# ad.net
KiCad netlist of a schematic drawn in Altium Designer
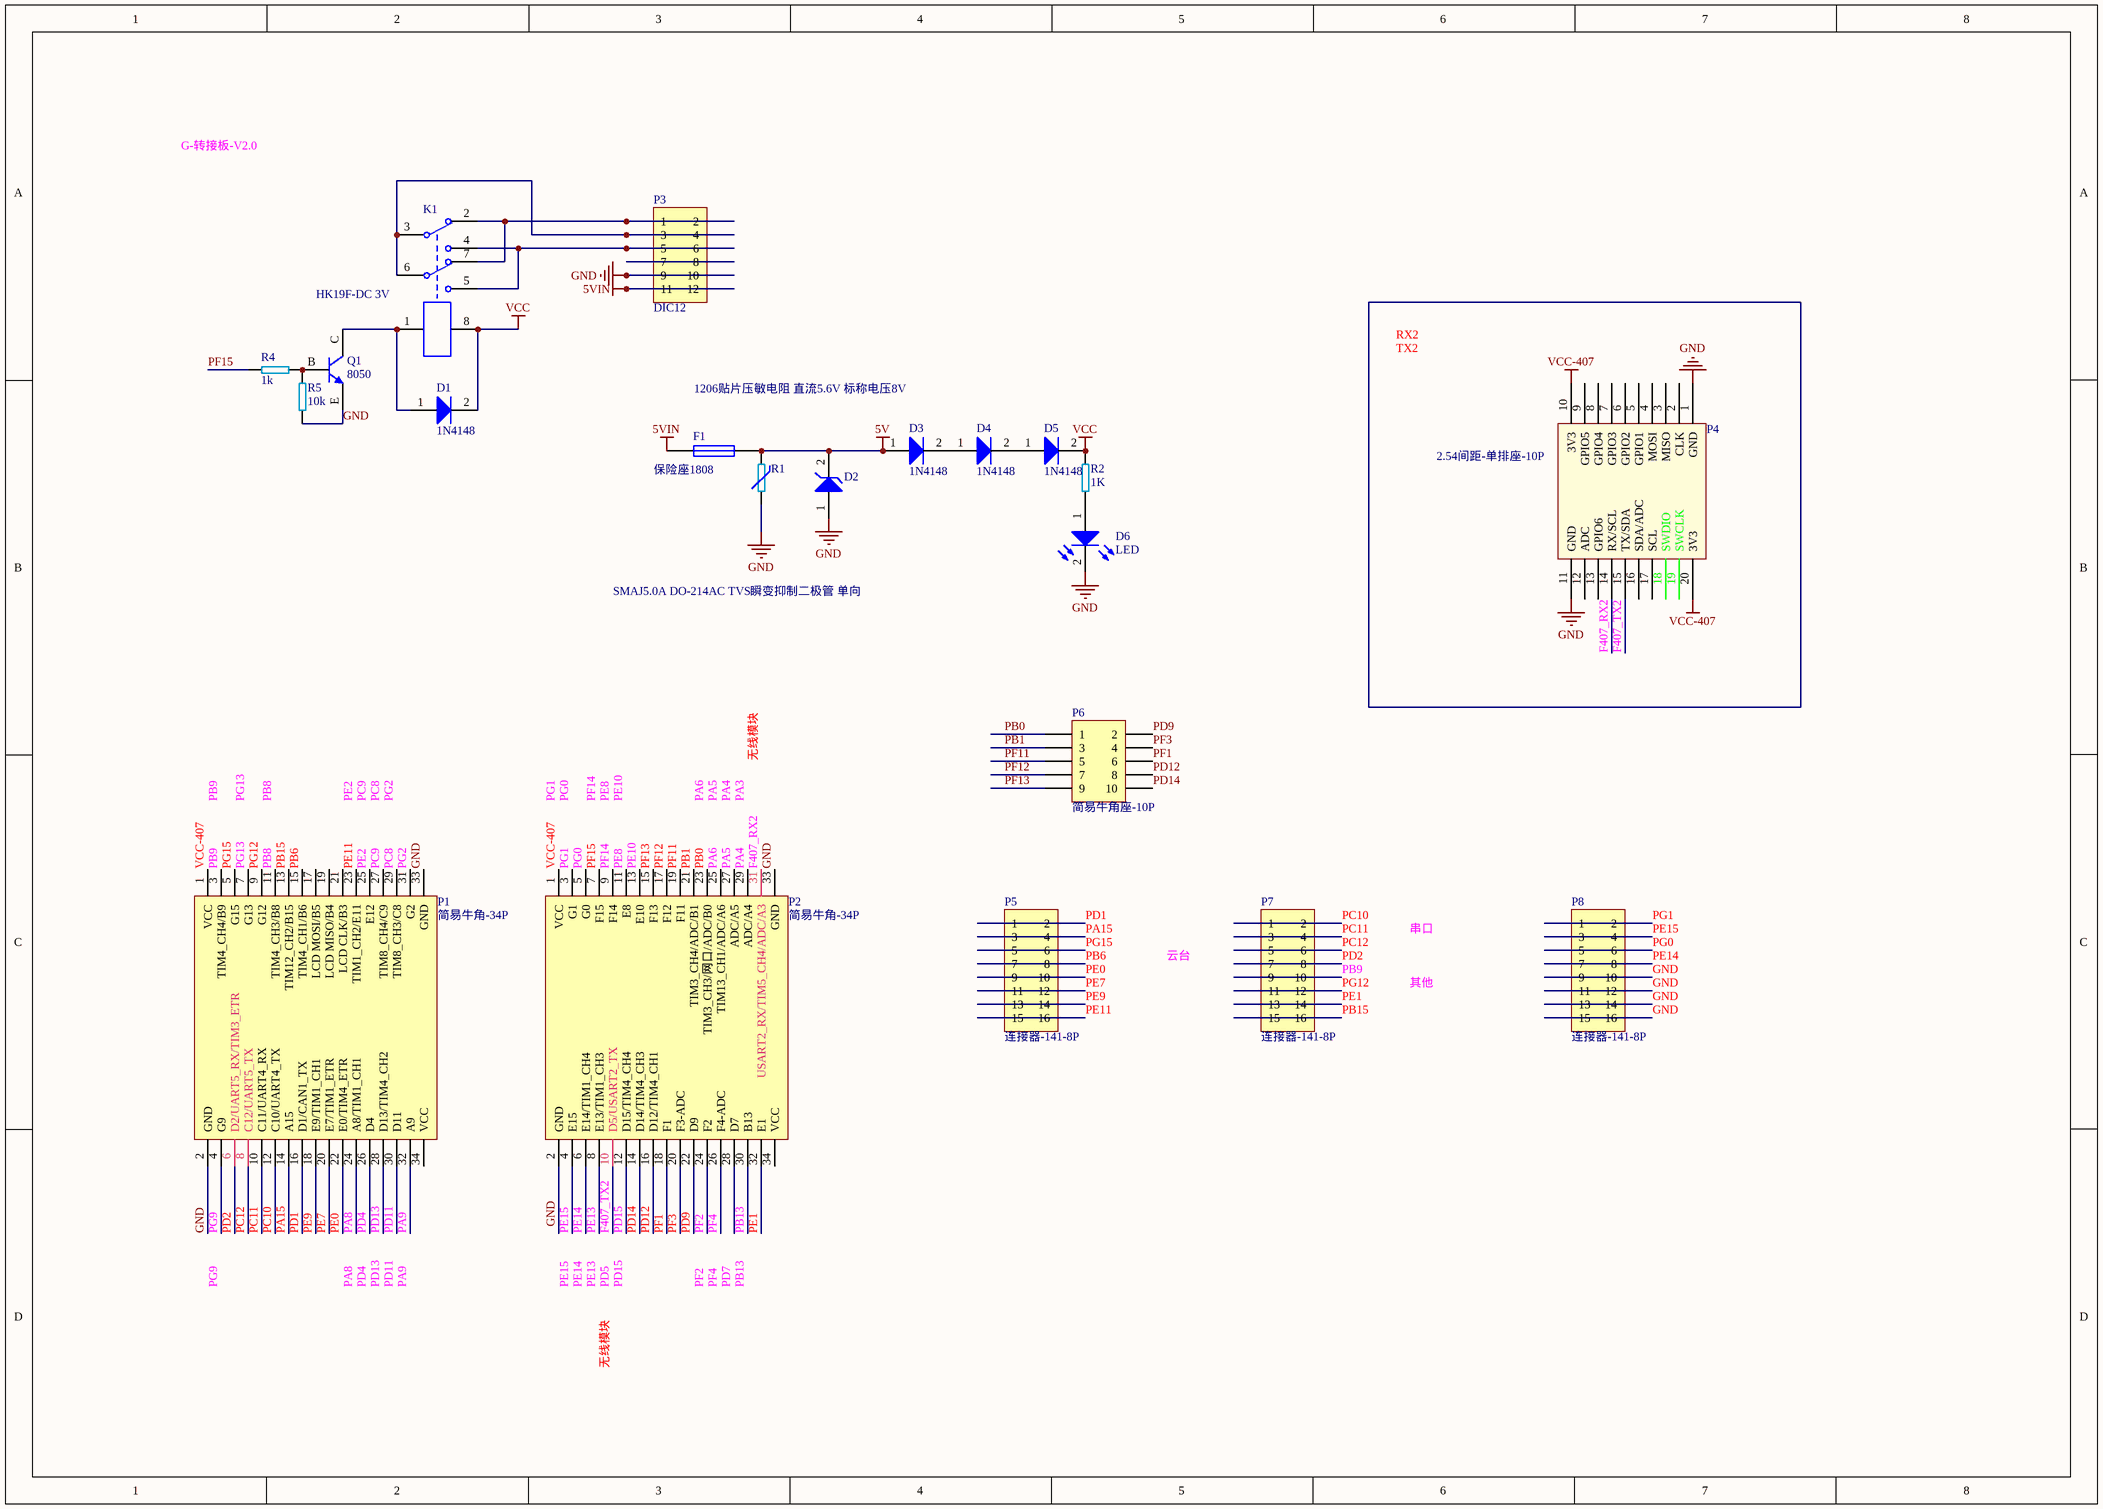
[diagram p0: ad.SchDoc]

(export (version "E")
  (design (tool "Eeschema 10.0.6"))
  (components
    (comp (ref "D1")
      (value "1N4148")
      (footprint "SOD123")
      (description "High Conductance Fast Diode")
      (fields (field (name "PUBLISHER") "Altium Limited"))
      (libsource (lib "base") (part "DD"))
    )
    (comp (ref "D2")
      (value "SMAJ5.0A DO-214AC TVS瞬变抑制二极管 单向")
      (footprint "SMA")
      (description "稳压管")
      (fields (field (name "PUBLISHER") "Altium Limited"))
      (libsource (lib "base") (part "TVS-SMA"))
    )
    (comp (ref "D3")
      (value "1N4148")
      (footprint "SOD123")
      (description "二极管")
      (fields (field (name "PUBLISHER") "Altium Limited"))
      (libsource (lib "base") (part "DD"))
    )
    (comp (ref "D4")
      (value "1N4148")
      (footprint "SOD123")
      (description "二极管")
      (fields (field (name "PUBLISHER") "Altium Limited"))
      (libsource (lib "base") (part "DD"))
    )
    (comp (ref "D5")
      (value "1N4148")
      (footprint "SOD123")
      (description "二极管")
      (fields (field (name "PUBLISHER") "Altium Limited"))
      (libsource (lib "base") (part "DD"))
    )
    (comp (ref "D6")
      (value "LED")
      (footprint "LED0603")
      (description "LED0603")
      (fields (field (name "PUBLISHER") "Altium Limited"))
      (libsource (lib "base") (part "LED0603"))
    )
    (comp (ref "F1")
      (value "保险座1808")
      (footprint "F1808-ZUO")
      (description "保险座")
      (fields (field (name "PUBLISHER") "Altium Limited"))
      (libsource (lib "base") (part "Fuse0805"))
    )
    (comp (ref "K1")
      (value "HK19F-DC 3V")
      (footprint "HK19F")
      (description "Dual-Pole Dual-Throw Relay")
      (fields (field (name "PUBLISHER") "Altium Limited"))
      (libsource (lib "base") (part "Relay-DPDT"))
    )
    (comp (ref "P1")
      (value "简易牛角-34P")
      (footprint "IDC2.54-LI-2x17P")
      (description "双排插座2.54间距-34P-带边框")
      (libsource (lib "base") (part "STM32F407-L"))
    )
    (comp (ref "P2")
      (value "简易牛角-34P")
      (footprint "IDC2.54-LI-2x17P")
      (description "双排插座2.54间距-34P-带边框")
      (libsource (lib "base") (part "STM32F407-R"))
    )
    (comp (ref "P3")
      (value "DIC12")
      (footprint "141V-6P")
      (description "连接器")
      (fields (field (name "PUBLISHER") "Altium Limited"))
      (libsource (lib "base") (part "DIC12"))
    )
    (comp (ref "P4")
      (value "2.54间距-单排座-10P")
      (footprint "SIP20-2-MODE")
      (description "单排针-10P")
      (libsource (lib "Schlib1") (part "PM-20-D"))
    )
    (comp (ref "P5")
      (value "连接器-141-8P")
      (footprint "141V-8P")
      (description "连接器")
      (fields (field (name "PUBLISHER") "Altium Limited"))
      (libsource (lib "base") (part "DIC16"))
    )
    (comp (ref "P6")
      (value "简易牛角座-10P")
      (footprint "IDC2.54-LI-10P")
      (description "连接器")
      (fields (field (name "PUBLISHER") "Altium Limited"))
      (libsource (lib "base") (part "DIC10"))
    )
    (comp (ref "P7")
      (value "连接器-141-8P")
      (footprint "141V-8P")
      (description "连接器")
      (fields (field (name "PUBLISHER") "Altium Limited"))
      (libsource (lib "base") (part "DIC16"))
    )
    (comp (ref "P8")
      (value "连接器-141-8P")
      (footprint "141V-8P")
      (description "连接器")
      (fields (field (name "PUBLISHER") "Altium Limited"))
      (libsource (lib "base") (part "DIC16"))
    )
    (comp (ref "Q1")
      (value "8050")
      (footprint "SOT-23")
      (description "NPN Bipolar Transistor")
      (fields (field (name "PUBLISHER") "Altium Limited"))
      (libsource (lib "base") (part "8050"))
    )
    (comp (ref "R1")
      (value "1206贴片压敏电阻 直流5.6V 标称电压8V")
      (footprint "R1206")
      (description "压敏电阻")
      (libsource (lib "base") (part "RV"))
    )
    (comp (ref "R2")
      (value "1K")
      (footprint "R0603")
      (description "贴片电阻")
      (libsource (lib "base") (part "R-0603"))
    )
    (comp (ref "R4") (value "1k") (footprint "R0603") (libsource (lib "base") (part "R-0603")))
    (comp (ref "R5")
      (value "10k")
      (footprint "R0603")
      (description "贴片电阻")
      (libsource (lib "base") (part "R-0603"))
    )
  )
  (nets
    (net (code "1") (name "/F407_RX2") (class "Default")
      (node (ref "P2") (pin "31") (pinfunction "USART2_RX/TIM5_CH4/ADC/A3_31") (pintype "passive"))
      (node (ref "P4") (pin "14") (pinfunction "RX/SCL_14") (pintype "passive"))
    )
    (net (code "2") (name "/F407_TX2") (class "Default")
      (node (ref "P2") (pin "10") (pinfunction "D5/USART2_TX_10") (pintype "passive"))
      (node (ref "P4") (pin "15") (pinfunction "TX/SDA_15") (pintype "passive"))
    )
    (net (code "5") (name "/PA4") (class "Default")
      (node (ref "P2") (pin "29") (pinfunction "ADC/A4_29") (pintype "passive"))
    )
    (net (code "6") (name "/PA5") (class "Default")
      (node (ref "P2") (pin "27") (pinfunction "ADC/A5_27") (pintype "passive"))
    )
    (net (code "7") (name "/PA6") (class "Default")
      (node (ref "P2") (pin "25") (pinfunction "TIM13_CH1/ADC/A6_25") (pintype "passive"))
    )
    (net (code "8") (name "/PA8") (class "Default")
      (node (ref "P1") (pin "24") (pinfunction "A8/TIM1_CH1_24") (pintype "passive"))
    )
    (net (code "9") (name "/PA9") (class "Default")
      (node (ref "P1") (pin "32") (pinfunction "A9_32") (pintype "passive"))
    )
    (net (code "10") (name "/PA15") (class "Default")
      (node (ref "P1") (pin "14") (pinfunction "A15_14") (pintype "passive"))
      (node (ref "P5") (pin "3") (pinfunction "3_3") (pintype "passive"))
      (node (ref "P5") (pin "4") (pinfunction "4_4") (pintype "passive"))
    )
    (net (code "11") (name "/PB0") (class "Default")
      (node (ref "P2") (pin "23") (pinfunction "TIM3_CH3/网口/ADC/B0_23") (pintype "passive"))
      (node (ref "P6") (pin "1") (pinfunction "1_1") (pintype "passive"))
    )
    (net (code "12") (name "/PB1") (class "Default")
      (node (ref "P2") (pin "21") (pinfunction "TIM3_CH4/ADC/B1_21") (pintype "passive"))
      (node (ref "P6") (pin "3") (pinfunction "3_3") (pintype "passive"))
    )
    (net (code "13") (name "/PB6") (class "Default")
      (node (ref "P1") (pin "15") (pinfunction "TIM4_CH1/B6_15") (pintype "passive"))
      (node (ref "P5") (pin "7") (pinfunction "7_7") (pintype "passive"))
      (node (ref "P5") (pin "8") (pinfunction "8_8") (pintype "passive"))
    )
    (net (code "14") (name "/PB8") (class "Default")
      (node (ref "P1") (pin "11") (pinfunction "TIM4_CH3/B8_11") (pintype "passive"))
    )
    (net (code "15") (name "/PB9") (class "Default")
      (node (ref "P1") (pin "3") (pinfunction "TIM4_CH4/B9_3") (pintype "passive"))
      (node (ref "P7") (pin "10") (pinfunction "10_10") (pintype "passive"))
      (node (ref "P7") (pin "9") (pinfunction "9_9") (pintype "passive"))
    )
    (net (code "16") (name "/PB13") (class "Default")
      (node (ref "P2") (pin "30") (pinfunction "B13_30") (pintype "passive"))
    )
    (net (code "17") (name "/PB15") (class "Default")
      (node (ref "P1") (pin "13") (pinfunction "TIM12_CH2/B15_13") (pintype "passive"))
      (node (ref "P7") (pin "15") (pinfunction "15_15") (pintype "passive"))
      (node (ref "P7") (pin "16") (pinfunction "16_16") (pintype "passive"))
    )
    (net (code "18") (name "/PC8") (class "Default")
      (node (ref "P1") (pin "29") (pinfunction "TIM8_CH3/C8_29") (pintype "passive"))
    )
    (net (code "19") (name "/PC9") (class "Default")
      (node (ref "P1") (pin "27") (pinfunction "TIM8_CH4/C9_27") (pintype "passive"))
    )
    (net (code "20") (name "/PC10") (class "Default")
      (node (ref "P1") (pin "12") (pinfunction "C10/UART4_TX_12") (pintype "passive"))
      (node (ref "P7") (pin "1") (pinfunction "1_1") (pintype "passive"))
      (node (ref "P7") (pin "2") (pinfunction "2_2") (pintype "passive"))
    )
    (net (code "21") (name "/PC11") (class "Default")
      (node (ref "P1") (pin "10") (pinfunction "C11/UART4_RX_10") (pintype "passive"))
      (node (ref "P7") (pin "3") (pinfunction "3_3") (pintype "passive"))
      (node (ref "P7") (pin "4") (pinfunction "4_4") (pintype "passive"))
    )
    (net (code "22") (name "/PC12") (class "Default")
      (node (ref "P1") (pin "8") (pinfunction "C12/UART5_TX_8") (pintype "passive"))
      (node (ref "P7") (pin "5") (pinfunction "5_5") (pintype "passive"))
      (node (ref "P7") (pin "6") (pinfunction "6_6") (pintype "passive"))
    )
    (net (code "23") (name "/PD1") (class "Default")
      (node (ref "P1") (pin "16") (pinfunction "D1/CAN1_TX_16") (pintype "passive"))
      (node (ref "P5") (pin "1") (pinfunction "1_1") (pintype "passive"))
      (node (ref "P5") (pin "2") (pinfunction "2_2") (pintype "passive"))
    )
    (net (code "24") (name "/PD2") (class "Default")
      (node (ref "P1") (pin "6") (pinfunction "D2/UART5_RX/TIM3_ETR_6") (pintype "passive"))
      (node (ref "P7") (pin "7") (pinfunction "7_7") (pintype "passive"))
      (node (ref "P7") (pin "8") (pinfunction "8_8") (pintype "passive"))
    )
    (net (code "25") (name "/PD4") (class "Default")
      (node (ref "P1") (pin "26") (pinfunction "D4_26") (pintype "passive"))
    )
    (net (code "28") (name "/PD9") (class "Default")
      (node (ref "P2") (pin "22") (pinfunction "D9_22") (pintype "passive"))
      (node (ref "P6") (pin "2") (pinfunction "2_2") (pintype "passive"))
    )
    (net (code "29") (name "/PD11") (class "Default")
      (node (ref "P1") (pin "30") (pinfunction "D11_30") (pintype "passive"))
    )
    (net (code "30") (name "/PD12") (class "Default")
      (node (ref "P2") (pin "16") (pinfunction "D12/TIM4_CH1_16") (pintype "passive"))
      (node (ref "P6") (pin "8") (pinfunction "8_8") (pintype "passive"))
    )
    (net (code "31") (name "/PD13") (class "Default")
      (node (ref "P1") (pin "28") (pinfunction "D13/TIM4_CH2_28") (pintype "passive"))
    )
    (net (code "32") (name "/PD14") (class "Default")
      (node (ref "P2") (pin "14") (pinfunction "D14/TIM4_CH3_14") (pintype "passive"))
      (node (ref "P6") (pin "10") (pinfunction "10_10") (pintype "passive"))
    )
    (net (code "33") (name "/PD15") (class "Default")
      (node (ref "P2") (pin "12") (pinfunction "D15/TIM4_CH4_12") (pintype "passive"))
    )
    (net (code "34") (name "/PE0") (class "Default")
      (node (ref "P1") (pin "22") (pinfunction "E0/TIM4_ETR_22") (pintype "passive"))
      (node (ref "P5") (pin "10") (pinfunction "10_10") (pintype "passive"))
      (node (ref "P5") (pin "9") (pinfunction "9_9") (pintype "passive"))
    )
    (net (code "35") (name "/PE1") (class "Default")
      (node (ref "P2") (pin "32") (pinfunction "E1_32") (pintype "passive"))
      (node (ref "P7") (pin "13") (pinfunction "13_13") (pintype "passive"))
      (node (ref "P7") (pin "14") (pinfunction "14_14") (pintype "passive"))
    )
    (net (code "36") (name "/PE2") (class "Default")
      (node (ref "P1") (pin "25") (pinfunction "E12_25") (pintype "passive"))
    )
    (net (code "37") (name "/PE7") (class "Default")
      (node (ref "P1") (pin "20") (pinfunction "E7/TIM1_ETR_20") (pintype "passive"))
      (node (ref "P5") (pin "11") (pinfunction "11_11") (pintype "passive"))
      (node (ref "P5") (pin "12") (pinfunction "12_12") (pintype "passive"))
    )
    (net (code "38") (name "/PE8") (class "Default")
      (node (ref "P2") (pin "11") (pinfunction "E8_11") (pintype "passive"))
    )
    (net (code "39") (name "/PE9") (class "Default")
      (node (ref "P1") (pin "18") (pinfunction "E9/TIM1_CH1_18") (pintype "passive"))
      (node (ref "P5") (pin "13") (pinfunction "13_13") (pintype "passive"))
      (node (ref "P5") (pin "14") (pinfunction "14_14") (pintype "passive"))
    )
    (net (code "40") (name "/PE10") (class "Default")
      (node (ref "P2") (pin "13") (pinfunction "E10_13") (pintype "passive"))
    )
    (net (code "41") (name "/PE11") (class "Default")
      (node (ref "P1") (pin "23") (pinfunction "TIM1_CH2/E11_23") (pintype "passive"))
      (node (ref "P5") (pin "15") (pinfunction "15_15") (pintype "passive"))
      (node (ref "P5") (pin "16") (pinfunction "16_16") (pintype "passive"))
    )
    (net (code "42") (name "/PE13") (class "Default")
      (node (ref "P2") (pin "8") (pinfunction "E13/TIM1_CH3_8") (pintype "passive"))
    )
    (net (code "43") (name "/PE14") (class "Default")
      (node (ref "P2") (pin "6") (pinfunction "E14/TIM1_CH4_6") (pintype "passive"))
      (node (ref "P8") (pin "7") (pinfunction "7_7") (pintype "passive"))
      (node (ref "P8") (pin "8") (pinfunction "8_8") (pintype "passive"))
    )
    (net (code "44") (name "/PE15") (class "Default")
      (node (ref "P2") (pin "4") (pinfunction "E15_4") (pintype "passive"))
      (node (ref "P8") (pin "3") (pinfunction "3_3") (pintype "passive"))
      (node (ref "P8") (pin "4") (pinfunction "4_4") (pintype "passive"))
    )
    (net (code "45") (name "/PF1") (class "Default")
      (node (ref "P2") (pin "18") (pinfunction "F1_18") (pintype "passive"))
      (node (ref "P6") (pin "6") (pinfunction "6_6") (pintype "passive"))
    )
    (net (code "46") (name "/PF2") (class "Default")
      (node (ref "P2") (pin "24") (pinfunction "F2_24") (pintype "passive"))
    )
    (net (code "47") (name "/PF3") (class "Default")
      (node (ref "P2") (pin "20") (pinfunction "F3-ADC_20") (pintype "passive"))
      (node (ref "P6") (pin "4") (pinfunction "4_4") (pintype "passive"))
    )
    (net (code "48") (name "/PF4") (class "Default")
      (node (ref "P2") (pin "26") (pinfunction "F4-ADC_26") (pintype "passive"))
    )
    (net (code "49") (name "/PF11") (class "Default")
      (node (ref "P2") (pin "19") (pinfunction "F11_19") (pintype "passive"))
      (node (ref "P6") (pin "5") (pinfunction "5_5") (pintype "passive"))
    )
    (net (code "50") (name "/PF12") (class "Default")
      (node (ref "P2") (pin "17") (pinfunction "F12_17") (pintype "passive"))
      (node (ref "P6") (pin "7") (pinfunction "7_7") (pintype "passive"))
    )
    (net (code "51") (name "/PF13") (class "Default")
      (node (ref "P2") (pin "15") (pinfunction "F13_15") (pintype "passive"))
      (node (ref "P6") (pin "9") (pinfunction "9_9") (pintype "passive"))
    )
    (net (code "52") (name "/PF14") (class "Default")
      (node (ref "P2") (pin "9") (pinfunction "F14_9") (pintype "passive"))
    )
    (net (code "53") (name "/PF15") (class "Default")
      (node (ref "P2") (pin "7") (pinfunction "F15_7") (pintype "passive"))
      (node (ref "R4") (pin "1") (pinfunction "1_1") (pintype "passive"))
    )
    (net (code "54") (name "/PG0") (class "Default")
      (node (ref "P2") (pin "5") (pinfunction "G0_5") (pintype "passive"))
      (node (ref "P8") (pin "5") (pinfunction "5_5") (pintype "passive"))
      (node (ref "P8") (pin "6") (pinfunction "6_6") (pintype "passive"))
    )
    (net (code "55") (name "/PG1") (class "Default")
      (node (ref "P2") (pin "3") (pinfunction "G1_3") (pintype "passive"))
      (node (ref "P8") (pin "1") (pinfunction "1_1") (pintype "passive"))
      (node (ref "P8") (pin "2") (pinfunction "2_2") (pintype "passive"))
    )
    (net (code "56") (name "/PG2") (class "Default")
      (node (ref "P1") (pin "31") (pinfunction "G2_31") (pintype "passive"))
    )
    (net (code "57") (name "/PG9") (class "Default")
      (node (ref "P1") (pin "4") (pinfunction "G9_4") (pintype "passive"))
    )
    (net (code "58") (name "/PG12") (class "Default")
      (node (ref "P1") (pin "9") (pinfunction "G12_9") (pintype "passive"))
      (node (ref "P7") (pin "11") (pinfunction "11_11") (pintype "passive"))
      (node (ref "P7") (pin "12") (pinfunction "12_12") (pintype "passive"))
    )
    (net (code "59") (name "/PG13") (class "Default")
      (node (ref "P1") (pin "7") (pinfunction "G13_7") (pintype "passive"))
    )
    (net (code "60") (name "/PG15") (class "Default")
      (node (ref "P1") (pin "5") (pinfunction "G15_5") (pintype "passive"))
      (node (ref "P5") (pin "5") (pinfunction "5_5") (pintype "passive"))
      (node (ref "P5") (pin "6") (pinfunction "6_6") (pintype "passive"))
    )
    (net (code "67") (name "5V") (class "Default")
      (node (ref "D2") (pin "2") (pinfunction "2_2") (pintype "passive"))
      (node (ref "D3") (pin "1") (pinfunction "A_1") (pintype "passive"))
      (node (ref "F1") (pin "2") (pinfunction "2_2") (pintype "passive"))
      (node (ref "R1") (pin "2") (pinfunction "2_2") (pintype "passive"))
    )
    (net (code "68") (name "5VIN") (class "Default")
      (node (ref "F1") (pin "1") (pinfunction "1_1") (pintype "passive"))
      (node (ref "P3") (pin "11") (pinfunction "11_11") (pintype "passive"))
      (node (ref "P3") (pin "12") (pinfunction "12_12") (pintype "passive"))
    )
    (net (code "69") (name "GND") (class "Default")
      (node (ref "D2") (pin "1") (pinfunction "1_1") (pintype "passive"))
      (node (ref "D6") (pin "2") (pinfunction "K_2") (pintype "passive"))
      (node (ref "P1") (pin "2") (pinfunction "GND_2") (pintype "passive"))
      (node (ref "P1") (pin "33") (pinfunction "GND_33") (pintype "passive"))
      (node (ref "P2") (pin "2") (pinfunction "GND_2") (pintype "passive"))
      (node (ref "P2") (pin "33") (pinfunction "GND_33") (pintype "passive"))
      (node (ref "P3") (pin "10") (pinfunction "10_10") (pintype "passive"))
      (node (ref "P3") (pin "9") (pinfunction "9_9") (pintype "passive"))
      (node (ref "P4") (pin "1") (pinfunction "GND_1") (pintype "passive"))
      (node (ref "P4") (pin "11") (pinfunction "GND_11") (pintype "passive"))
      (node (ref "P8") (pin "10") (pinfunction "10_10") (pintype "passive"))
      (node (ref "P8") (pin "11") (pinfunction "11_11") (pintype "passive"))
      (node (ref "P8") (pin "12") (pinfunction "12_12") (pintype "passive"))
      (node (ref "P8") (pin "13") (pinfunction "13_13") (pintype "passive"))
      (node (ref "P8") (pin "14") (pinfunction "14_14") (pintype "passive"))
      (node (ref "P8") (pin "15") (pinfunction "15_15") (pintype "passive"))
      (node (ref "P8") (pin "16") (pinfunction "16_16") (pintype "passive"))
      (node (ref "P8") (pin "9") (pinfunction "9_9") (pintype "passive"))
      (node (ref "Q1") (pin "E") (pinfunction "E_E") (pintype "passive"))
      (node (ref "R1") (pin "1") (pinfunction "1_1") (pintype "passive"))
      (node (ref "R5") (pin "1") (pinfunction "1_1") (pintype "passive"))
    )
    (net (code "70") (name "Net-(D1-A)") (class "Default")
      (node (ref "D1") (pin "1") (pinfunction "A_1") (pintype "passive"))
      (node (ref "K1") (pin "1") (pinfunction "1_1") (pintype "passive"))
      (node (ref "Q1") (pin "C") (pinfunction "C_C") (pintype "passive"))
    )
    (net (code "71") (name "Net-(D3-K)") (class "Default")
      (node (ref "D3") (pin "2") (pinfunction "K_2") (pintype "passive"))
      (node (ref "D4") (pin "1") (pinfunction "A_1") (pintype "passive"))
    )
    (net (code "72") (name "Net-(D4-K)") (class "Default")
      (node (ref "D4") (pin "2") (pinfunction "K_2") (pintype "passive"))
      (node (ref "D5") (pin "1") (pinfunction "A_1") (pintype "passive"))
    )
    (net (code "73") (name "Net-(D6-A)") (class "Default")
      (node (ref "D6") (pin "1") (pinfunction "A_1") (pintype "passive"))
      (node (ref "R2") (pin "1") (pinfunction "1_1") (pintype "passive"))
    )
    (net (code "74") (name "Net-(K1-Pad2)") (class "Default")
      (node (ref "K1") (pin "2") (pinfunction "2_2") (pintype "passive"))
      (node (ref "K1") (pin "7") (pinfunction "7_7") (pintype "passive"))
      (node (ref "P3") (pin "1") (pinfunction "1_1") (pintype "passive"))
      (node (ref "P3") (pin "2") (pinfunction "2_2") (pintype "passive"))
    )
    (net (code "75") (name "Net-(K1-Pad3)") (class "Default")
      (node (ref "K1") (pin "3") (pinfunction "3_3") (pintype "passive"))
      (node (ref "K1") (pin "6") (pinfunction "6_6") (pintype "passive"))
      (node (ref "P3") (pin "3") (pinfunction "3_3") (pintype "passive"))
      (node (ref "P3") (pin "4") (pinfunction "4_4") (pintype "passive"))
    )
    (net (code "76") (name "Net-(K1-Pad4)") (class "Default")
      (node (ref "K1") (pin "4") (pinfunction "4_4") (pintype "passive"))
      (node (ref "K1") (pin "5") (pinfunction "5_5") (pintype "passive"))
      (node (ref "P3") (pin "5") (pinfunction "5_5") (pintype "passive"))
      (node (ref "P3") (pin "6") (pinfunction "6_6") (pintype "passive"))
    )
    (net (code "77") (name "Net-(P3-Pad7)") (class "Default")
      (node (ref "P3") (pin "7") (pinfunction "7_7") (pintype "passive"))
      (node (ref "P3") (pin "8") (pinfunction "8_8") (pintype "passive"))
    )
    (net (code "78") (name "Net-(Q1-PadB)") (class "Default")
      (node (ref "Q1") (pin "B") (pinfunction "B_B") (pintype "passive"))
      (node (ref "R4") (pin "2") (pinfunction "2_2") (pintype "passive"))
      (node (ref "R5") (pin "2") (pinfunction "2_2") (pintype "passive"))
    )
    (net (code "79") (name "VCC") (class "Default")
      (node (ref "D1") (pin "2") (pinfunction "K_2") (pintype "passive"))
      (node (ref "D5") (pin "2") (pinfunction "K_2") (pintype "passive"))
      (node (ref "K1") (pin "8") (pinfunction "8_8") (pintype "passive"))
      (node (ref "R2") (pin "2") (pinfunction "2_2") (pintype "passive"))
    )
    (net (code "80") (name "VCC-407") (class "Default")
      (node (ref "P1") (pin "1") (pinfunction "VCC_1") (pintype "passive"))
      (node (ref "P2") (pin "1") (pinfunction "VCC_1") (pintype "passive"))
      (node (ref "P4") (pin "10") (pinfunction "3V3_10") (pintype "passive"))
      (node (ref "P4") (pin "20") (pinfunction "3V3_20") (pintype "passive"))
    )
    (net (code "81") (name "unconnected-(P1-LCD_CLK{slash}B3-Pad21)") (class "Default")
      (node (ref "P1") (pin "21") (pinfunction "LCD_CLK/B3_21") (pintype "passive"))
    )
    (net (code "82") (name "unconnected-(P1-LCD_MISO{slash}B4-Pad19)") (class "Default")
      (node (ref "P1") (pin "19") (pinfunction "LCD_MISO/B4_19") (pintype "passive"))
    )
    (net (code "83") (name "unconnected-(P1-LCD_MOSI{slash}B5-Pad17)") (class "Default")
      (node (ref "P1") (pin "17") (pinfunction "LCD_MOSI/B5_17") (pintype "passive"))
    )
    (net (code "84") (name "unconnected-(P1-VCC-Pad34)") (class "Default")
      (node (ref "P1") (pin "34") (pinfunction "VCC_34") (pintype "passive"))
    )
    (net (code "85") (name "unconnected-(P2-D7-Pad28)") (class "Default")
      (node (ref "P2") (pin "28") (pinfunction "D7_28") (pintype "passive"))
    )
    (net (code "86") (name "unconnected-(P2-VCC-Pad34)") (class "Default")
      (node (ref "P2") (pin "34") (pinfunction "VCC_34") (pintype "passive"))
    )
    (net (code "87") (name "unconnected-(P4-ADC-Pad12)") (class "Default")
      (node (ref "P4") (pin "12") (pinfunction "ADC_12") (pintype "passive"))
    )
    (net (code "88") (name "unconnected-(P4-CLK-Pad2)") (class "Default")
      (node (ref "P4") (pin "2") (pinfunction "CLK_2") (pintype "passive"))
    )
    (net (code "89") (name "unconnected-(P4-GPIO1-Pad5)") (class "Default")
      (node (ref "P4") (pin "5") (pinfunction "GPIO1_5") (pintype "passive"))
    )
    (net (code "90") (name "unconnected-(P4-GPIO2-Pad6)") (class "Default")
      (node (ref "P4") (pin "6") (pinfunction "GPIO2_6") (pintype "passive"))
    )
    (net (code "91") (name "unconnected-(P4-GPIO3-Pad7)") (class "Default")
      (node (ref "P4") (pin "7") (pinfunction "GPIO3_7") (pintype "passive"))
    )
    (net (code "92") (name "unconnected-(P4-GPIO4-Pad8)") (class "Default")
      (node (ref "P4") (pin "8") (pinfunction "GPIO4_8") (pintype "passive"))
    )
    (net (code "93") (name "unconnected-(P4-GPIO5-Pad9)") (class "Default")
      (node (ref "P4") (pin "9") (pinfunction "GPIO5_9") (pintype "passive"))
    )
    (net (code "94") (name "unconnected-(P4-GPIO6-Pad13)") (class "Default")
      (node (ref "P4") (pin "13") (pinfunction "GPIO6_13") (pintype "passive"))
    )
    (net (code "95") (name "unconnected-(P4-MISO-Pad3)") (class "Default")
      (node (ref "P4") (pin "3") (pinfunction "MISO_3") (pintype "passive"))
    )
    (net (code "96") (name "unconnected-(P4-MOSI-Pad4)") (class "Default")
      (node (ref "P4") (pin "4") (pinfunction "MOSI_4") (pintype "passive"))
    )
    (net (code "97") (name "unconnected-(P4-SCL-Pad17)") (class "Default")
      (node (ref "P4") (pin "17") (pinfunction "SCL_17") (pintype "passive"))
    )
    (net (code "98") (name "unconnected-(P4-SDA{slash}ADC-Pad16)") (class "Default")
      (node (ref "P4") (pin "16") (pinfunction "SDA/ADC_16") (pintype "passive"))
    )
    (net (code "99") (name "unconnected-(P4-SWCLK-Pad19)") (class "Default")
      (node (ref "P4") (pin "19") (pinfunction "SWCLK_19") (pintype "passive"))
    )
    (net (code "100") (name "unconnected-(P4-SWDIO-Pad18)") (class "Default")
      (node (ref "P4") (pin "18") (pinfunction "SWDIO_18") (pintype "passive"))
    )
  )
)
